# MCU.net
KiCad netlist of a schematic drawn in Altium Designer
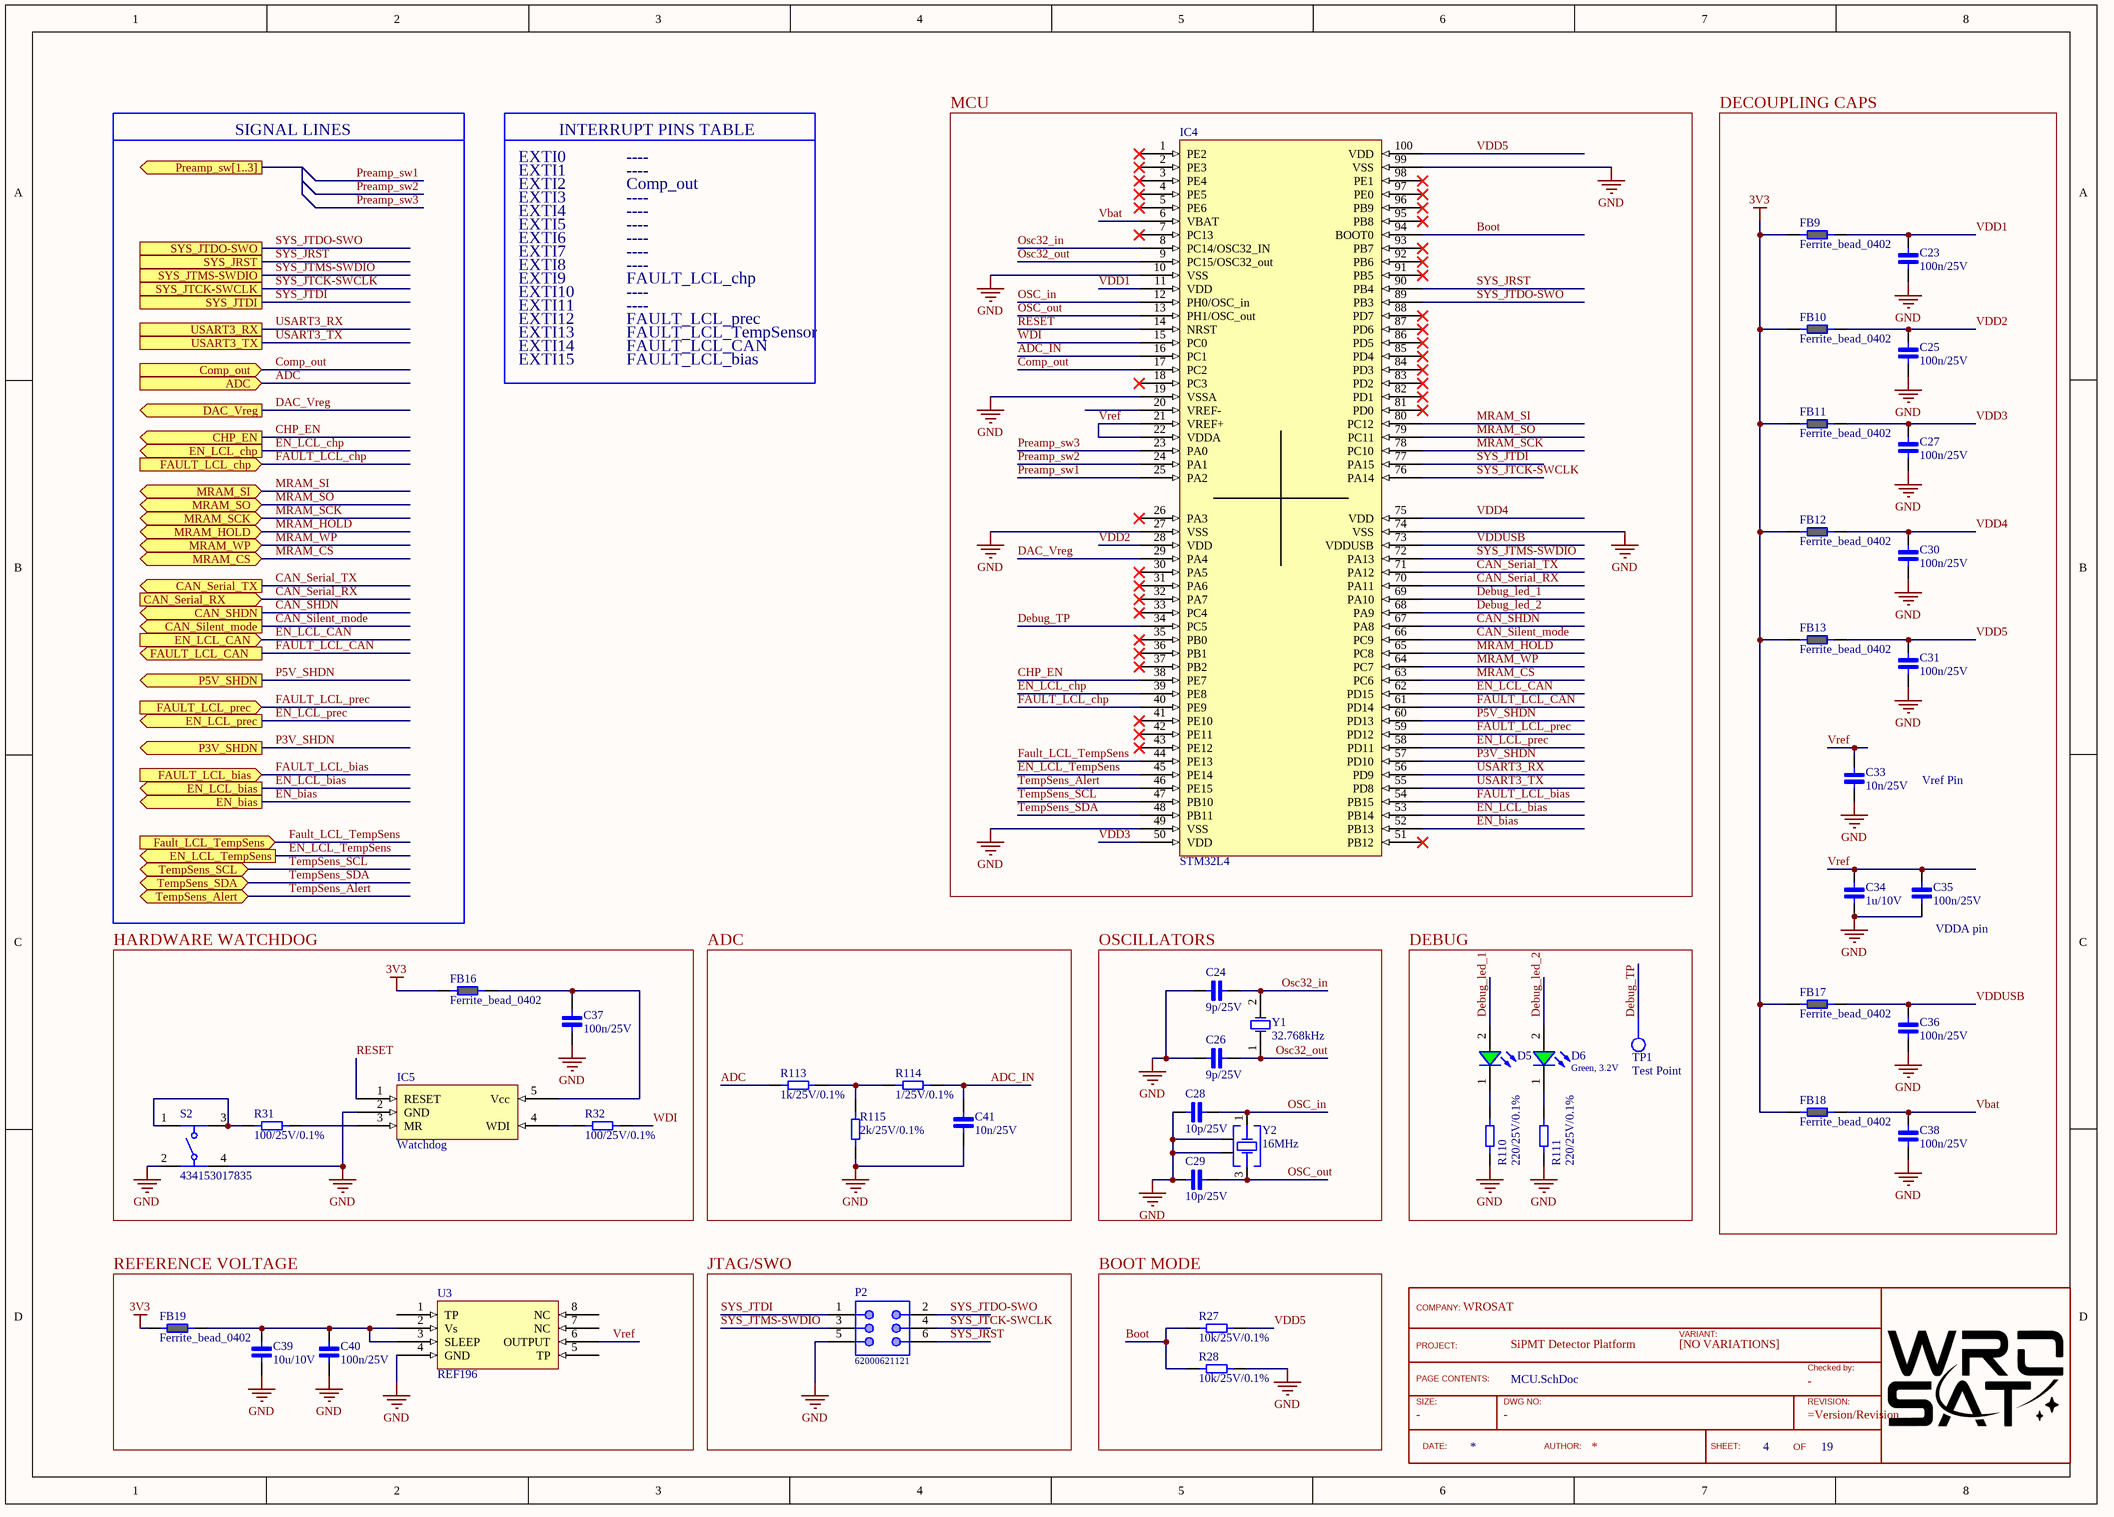
[diagram p0: MCU.SchDoc]

(export (version "E")
  (design (tool "Eeschema 10.0.6"))
  (components
    (comp (ref "C23")
      (value "100n/25V")
      (footprint "Cap_0402")
      (description "Ceramic Capacitor 100n / 0402 / 25V / ±5%, Wurth Elektronik MLCC")
      (libsource (lib "Cubesat_lib") (part "Cap_0402_100n"))
    )
    (comp (ref "C24")
      (value "9p/25V")
      (footprint "Cap_0402")
      (description "0402 / 25V / ±5%, Wurth Elektronik MLCC")
      (libsource (lib "Cubesat_lib") (part "Cap_0402_9p"))
    )
    (comp (ref "C25")
      (value "100n/25V")
      (footprint "Cap_0402")
      (description "Ceramic Capacitor 100n / 0402 / 25V / ±5%, Wurth Elektronik MLCC")
      (libsource (lib "Cubesat_lib") (part "Cap_0402_100n"))
    )
    (comp (ref "C26")
      (value "9p/25V")
      (footprint "Cap_0402")
      (description "0402 / 25V / ±5%, Wurth Elektronik MLCC")
      (libsource (lib "Cubesat_lib") (part "Cap_0402_9p"))
    )
    (comp (ref "C27")
      (value "100n/25V")
      (footprint "Cap_0402")
      (description "Ceramic Capacitor 100n / 0402 / 25V / ±5%, Wurth Elektronik MLCC")
      (libsource (lib "Cubesat_lib") (part "Cap_0402_100n"))
    )
    (comp (ref "C28")
      (value "10p/25V")
      (footprint "Cap_0402")
      (description "0402 / 25V / ±5%, Wurth Elektronik MLCC")
      (libsource (lib "Cubesat_lib") (part "Cap_0402_10p"))
    )
    (comp (ref "C29")
      (value "10p/25V")
      (footprint "Cap_0402")
      (description "0402 / 25V / ±5%, Wurth Elektronik MLCC")
      (libsource (lib "Cubesat_lib") (part "Cap_0402_10p"))
    )
    (comp (ref "C30")
      (value "100n/25V")
      (footprint "Cap_0402")
      (description "Ceramic Capacitor 100n / 0402 / 25V / ±5%, Wurth Elektronik MLCC")
      (libsource (lib "Cubesat_lib") (part "Cap_0402_100n"))
    )
    (comp (ref "C31")
      (value "100n/25V")
      (footprint "Cap_0402")
      (description "Ceramic Capacitor 100n / 0402 / 25V / ±5%, Wurth Elektronik MLCC")
      (libsource (lib "Cubesat_lib") (part "Cap_0402_100n"))
    )
    (comp (ref "C33")
      (value "10n/25V")
      (footprint "Cap_0402")
      (description "Ceramic Capacitor 10n / 0402 / 25V / ±5%, Wurth Elektronik MLCC")
      (libsource (lib "Cubesat_lib") (part "Cap_0402_10n"))
    )
    (comp (ref "C34")
      (value "1u/10V")
      (footprint "Cap_0402")
      (description "Ceramic Capacitor 1uF / 0402 / 10V / ±5%, Wurth Elektronik MLCC")
      (libsource (lib "Cubesat_lib") (part "Cap_0402_1u"))
    )
    (comp (ref "C35")
      (value "100n/25V")
      (footprint "Cap_0402")
      (description "Ceramic Capacitor 100n / 0402 / 25V / ±5%, Wurth Elektronik MLCC")
      (libsource (lib "Cubesat_lib") (part "Cap_0402_100n"))
    )
    (comp (ref "C36")
      (value "100n/25V")
      (footprint "Cap_0402")
      (description "Ceramic Capacitor 100n / 0402 / 25V / ±5%, Wurth Elektronik MLCC")
      (libsource (lib "Cubesat_lib") (part "Cap_0402_100n"))
    )
    (comp (ref "C37")
      (value "100n/25V")
      (footprint "Cap_0402")
      (description "Ceramic Capacitor 100n / 0402 / 25V / ±5%, Wurth Elektronik MLCC")
      (libsource (lib "Cubesat_lib") (part "Cap_0402_100n"))
    )
    (comp (ref "C38")
      (value "100n/25V")
      (footprint "Cap_0402")
      (description "Ceramic Capacitor 100n / 0402 / 25V / ±5%, Wurth Elektronik MLCC")
      (libsource (lib "Cubesat_lib") (part "Cap_0402_100n"))
    )
    (comp (ref "C39")
      (value "10u/10V")
      (footprint "CAP_0603")
      (description "Ceramic Capacitor 10uF / 0603 / 10V / ±5%, Wurth Elektronik MLCC")
      (libsource (lib "Cubesat_lib") (part "Cap_0603_10u"))
    )
    (comp (ref "C40")
      (value "100n/25V")
      (footprint "Cap_0402")
      (description "Ceramic Capacitor 100n / 0402 / 25V / ±5%, Wurth Elektronik MLCC")
      (libsource (lib "Cubesat_lib") (part "Cap_0402_100n"))
    )
    (comp (ref "C41")
      (value "10n/25V")
      (footprint "CAP_0603")
      (description "Ceramic Capacitor 10n / 0603 / 25V / ±5%, Wurth Elektronik MLCC")
      (libsource (lib "Cubesat_lib") (part "Cap_0603_10n"))
    )
    (comp (ref "D5")
      (value "Green, 3.2V")
      (footprint "WL-SMCW_0603_H=0.7mm")
      (description "WL-SMCW SMT Mono-color Chip LED Waterclear, size 0603, Green, 3.2V, 140deg")
      (fields (field (name "PART NUMBER") "150060GS75000") (field (name "PUBLISHER") "Wurth Elektronik"))
      (libsource (lib "LEDS") (part "150060GS75000"))
    )
    (comp (ref "D6")
      (value "Green, 3.2V")
      (footprint "WL-SMCW_0603_H=0.7mm")
      (description "WL-SMCW SMT Mono-color Chip LED Waterclear, size 0603, Green, 3.2V, 140deg")
      (fields (field (name "PART NUMBER") "150060GS75000") (field (name "PUBLISHER") "Wurth Elektronik"))
      (libsource (lib "LEDS") (part "150060GS75000"))
    )
    (comp (ref "FB9")
      (value "Ferrite_bead_0402")
      (footprint "FERRITE_0402")
      (description "Ferrite bead, wurth 74269241102")
      (libsource (lib "Cubesat_lib") (part "Ferrite_bead_0402"))
    )
    (comp (ref "FB10")
      (value "Ferrite_bead_0402")
      (footprint "FERRITE_0402")
      (description "Ferrite bead, wurth 74269241102")
      (libsource (lib "Cubesat_lib") (part "Ferrite_bead_0402"))
    )
    (comp (ref "FB11")
      (value "Ferrite_bead_0402")
      (footprint "FERRITE_0402")
      (description "Ferrite bead, wurth 74269241102")
      (libsource (lib "Cubesat_lib") (part "Ferrite_bead_0402"))
    )
    (comp (ref "FB12")
      (value "Ferrite_bead_0402")
      (footprint "FERRITE_0402")
      (description "Ferrite bead, wurth 74269241102")
      (libsource (lib "Cubesat_lib") (part "Ferrite_bead_0402"))
    )
    (comp (ref "FB13")
      (value "Ferrite_bead_0402")
      (footprint "FERRITE_0402")
      (description "Ferrite bead, wurth 74269241102")
      (libsource (lib "Cubesat_lib") (part "Ferrite_bead_0402"))
    )
    (comp (ref "FB16")
      (value "Ferrite_bead_0402")
      (footprint "FERRITE_0402")
      (description "Ferrite bead, wurth 74269241102")
      (libsource (lib "Cubesat_lib") (part "Ferrite_bead_0402"))
    )
    (comp (ref "FB17")
      (value "Ferrite_bead_0402")
      (footprint "FERRITE_0402")
      (description "Ferrite bead, wurth 74269241102")
      (libsource (lib "Cubesat_lib") (part "Ferrite_bead_0402"))
    )
    (comp (ref "FB18")
      (value "Ferrite_bead_0402")
      (footprint "FERRITE_0402")
      (description "Ferrite bead, wurth 74269241102")
      (libsource (lib "Cubesat_lib") (part "Ferrite_bead_0402"))
    )
    (comp (ref "FB19")
      (value "Ferrite_bead_0402")
      (footprint "FERRITE_0402")
      (description "Ferrite bead, wurth 74269241102")
      (libsource (lib "Cubesat_lib") (part "Ferrite_bead_0402"))
    )
    (comp (ref "IC4")
      (value "STM32L4")
      (footprint "LQFP100")
      (description "Microcontroller STM32")
      (libsource (lib "Cubesat_lib") (part "STM32L476VGT6"))
    )
    (comp (ref "IC5")
      (value "Watchdog")
      (footprint "SOT-23-5")
      (description "Watchdog, 5-Pin Microprocessor Supervisory Circuits With\r\nWatchdog Timer and Manual Reset")
      (libsource (lib "Cubesat_lib") (part "MAX823"))
    )
    (comp (ref "P2")
      (value "62000621121")
      (footprint "62000621121")
      (description "WR-PHD Pin Header, THT, pitch 2mm, Dual Row, Vertical, 6p")
      (fields (field (name "MANUFACTURER") "Wurth Elektronik"))
      (libsource (lib "goldpin") (part "62000621121"))
    )
    (comp (ref "R27")
      (value "10k/25V/0.1%")
      (footprint "RES_0402")
      (description "Vishay, thin film resistor 10k/25V/0.1%")
      (libsource (lib "Cubesat_lib") (part "Res_0402_10k"))
    )
    (comp (ref "R28")
      (value "10k/25V/0.1%")
      (footprint "RES_0402")
      (description "Vishay, thin film resistor 10k/25V/0.1%")
      (libsource (lib "Cubesat_lib") (part "Res_0402_10k"))
    )
    (comp (ref "R31")
      (value "100/25V/0.1%")
      (footprint "RES_0402")
      (description "Vishay, thin film resistor 100/25V/0.1%")
      (libsource (lib "Cubesat_lib") (part "Res_0402_100"))
    )
    (comp (ref "R32")
      (value "100/25V/0.1%")
      (footprint "RES_0402")
      (description "Vishay, thin film resistor 100/25V/0.1%")
      (libsource (lib "Cubesat_lib") (part "Res_0402_100"))
    )
    (comp (ref "R110")
      (value "220/25V/0.1%")
      (footprint "RES_0402")
      (description "Vishay, thin film resistor 1/25V/0.1%")
      (libsource (lib "Cubesat_lib") (part "Res_0402_1"))
    )
    (comp (ref "R111")
      (value "220/25V/0.1%")
      (footprint "RES_0402")
      (description "Vishay, thin film resistor 1/25V/0.1%")
      (libsource (lib "Cubesat_lib") (part "Res_0402_1"))
    )
    (comp (ref "R113")
      (value "1k/25V/0.1%")
      (footprint "RES_0402")
      (description "Vishay, thin film resistor 1k/25V/0.1%")
      (libsource (lib "Cubesat_lib") (part "Res_0402_1k"))
    )
    (comp (ref "R114")
      (value "1/25V/0.1%")
      (footprint "RES_0402")
      (description "Vishay, thin film resistor 1/25V/0.1%")
      (libsource (lib "") (part "Res_0402_1_1"))
    )
    (comp (ref "R115")
      (value "2k/25V/0.1%")
      (footprint "RES_0402")
      (description "Vishay, thin film resistor 2k/25V/0.1%")
      (libsource (lib "") (part "Res_0402_1k_1"))
    )
    (comp (ref "S2")
      (value "434153017835")
      (footprint "434153017835")
      (description "WS-TASV J-Bend SMT Tact Switch, 3.5x2.9x1.7mm, 350gf")
      (fields (field (name "MANUFACTURER") "Wurth Elektronik"))
      (libsource (lib "tact_switches") (part "434153017835"))
    )
    (comp (ref "TP1")
      (value "Test Point")
      (footprint "Test Point SMT")
      (libsource (lib "Cubesat_lib") (part "Test Point"))
    )
    (comp (ref "U3")
      (value "REF196")
      (footprint "SOIC8")
      (description "Precision Micropower,\r\nLow Dropout Voltage References")
      (libsource (lib "Cubesat_lib") (part "REF196"))
    )
    (comp (ref "Y1")
      (value "32.768kHz")
      (footprint "WE-XTAL_IQXC-25")
      (description "WE-XTAL Watch Crystal, SMT, IQXC-25, 32.768kHz, +/-10ppm")
      (fields
        (field (name "MANUFACTURER PART NUMBER") "830062558")
        (field (name "MANUFACTURER") "Wurth Elektronik")
      )
      (libsource (lib "32khz_crystal") (part "830062558"))
    )
    (comp (ref "Y2")
      (value "16MHz")
      (footprint "WE-XTAL_CFPX-218")
      (description "WE-XTAL Quartz Crystal, SMT, CFPX-218, 16MHz, +/-20ppm")
      (fields
        (field (name "MANUFACTURER PART NUMBER") "830069392")
        (field (name "MANUFACTURER") "Wurth Elektronik")
      )
      (libsource (lib "HSE_crystal") (part "830069392"))
    )
  )
  (nets
    (net (code "1") (name "/ADC") (class "Default")
      (node (ref "R113") (pin "1") (pinfunction "1_1") (pintype "passive"))
    )
    (net (code "2") (name "/ADC_IN") (class "Default")
      (node (ref "C41") (pin "2") (pinfunction "2_2") (pintype "passive"))
      (node (ref "IC4") (pin "16") (pinfunction "PC1_16") (pintype "input"))
      (node (ref "R114") (pin "2") (pinfunction "2_2") (pintype "passive"))
    )
    (net (code "3") (name "/Boot") (class "Default")
      (node (ref "IC4") (pin "94") (pinfunction "BOOT0_94") (pintype "input"))
      (node (ref "R27") (pin "1") (pinfunction "1_1") (pintype "passive"))
      (node (ref "R28") (pin "1") (pinfunction "1_1") (pintype "passive"))
    )
    (net (code "4") (name "/CAN_SHDN") (class "Default")
      (node (ref "IC4") (pin "67") (pinfunction "PA8_67") (pintype "input"))
    )
    (net (code "5") (name "/CAN_Serial_RX") (class "Default")
      (node (ref "IC4") (pin "70") (pinfunction "PA11_70") (pintype "input"))
    )
    (net (code "6") (name "/CAN_Serial_TX") (class "Default")
      (node (ref "IC4") (pin "71") (pinfunction "PA12_71") (pintype "input"))
    )
    (net (code "7") (name "/CAN_Silent_mode") (class "Default")
      (node (ref "IC4") (pin "66") (pinfunction "PC9_66") (pintype "input"))
    )
    (net (code "8") (name "/CHP_EN") (class "Default")
      (node (ref "IC4") (pin "38") (pinfunction "PE7_38") (pintype "input"))
    )
    (net (code "9") (name "/Comp_out") (class "Default")
      (node (ref "IC4") (pin "17") (pinfunction "PC2_17") (pintype "input"))
    )
    (net (code "10") (name "/DAC_Vreg") (class "Default")
      (node (ref "IC4") (pin "29") (pinfunction "PA4_29") (pintype "input"))
    )
    (net (code "11") (name "/Debug_TP") (class "Default")
      (node (ref "IC4") (pin "34") (pinfunction "PC5_34") (pintype "input"))
      (node (ref "TP1") (pin "1") (pinfunction "1_1") (pintype "passive"))
    )
    (net (code "12") (name "/Debug_led_1") (class "Default")
      (node (ref "D5") (pin "2") (pinfunction "A_2") (pintype "passive"))
      (node (ref "IC4") (pin "69") (pinfunction "PA10_69") (pintype "input"))
    )
    (net (code "13") (name "/Debug_led_2") (class "Default")
      (node (ref "D6") (pin "2") (pinfunction "A_2") (pintype "passive"))
      (node (ref "IC4") (pin "68") (pinfunction "PA9_68") (pintype "input"))
    )
    (net (code "14") (name "/EN_LCL_CAN") (class "Default")
      (node (ref "IC4") (pin "62") (pinfunction "PD15_62") (pintype "input"))
    )
    (net (code "15") (name "/EN_LCL_TempSens") (class "Default")
      (node (ref "IC4") (pin "45") (pinfunction "PE14_45") (pintype "input"))
    )
    (net (code "16") (name "/EN_LCL_bias") (class "Default")
      (node (ref "IC4") (pin "53") (pinfunction "PB14_53") (pintype "input"))
    )
    (net (code "17") (name "/EN_LCL_chp") (class "Default")
      (node (ref "IC4") (pin "39") (pinfunction "PE8_39") (pintype "input"))
    )
    (net (code "18") (name "/EN_LCL_prec") (class "Default")
      (node (ref "IC4") (pin "58") (pinfunction "PD11_58") (pintype "input"))
    )
    (net (code "19") (name "/EN_bias") (class "Default")
      (node (ref "IC4") (pin "52") (pinfunction "PB13_52") (pintype "input"))
    )
    (net (code "20") (name "/FAULT_LCL_CAN") (class "Default")
      (node (ref "IC4") (pin "61") (pinfunction "PD14_61") (pintype "input"))
    )
    (net (code "21") (name "/FAULT_LCL_bias") (class "Default")
      (node (ref "IC4") (pin "54") (pinfunction "PB15_54") (pintype "input"))
    )
    (net (code "22") (name "/FAULT_LCL_chp") (class "Default")
      (node (ref "IC4") (pin "40") (pinfunction "PE9_40") (pintype "input"))
    )
    (net (code "23") (name "/FAULT_LCL_prec") (class "Default")
      (node (ref "IC4") (pin "59") (pinfunction "PD12_59") (pintype "input"))
    )
    (net (code "24") (name "/Fault_LCL_TempSens") (class "Default")
      (node (ref "IC4") (pin "44") (pinfunction "PE13_44") (pintype "input"))
    )
    (net (code "25") (name "/MRAM_CS") (class "Default")
      (node (ref "IC4") (pin "63") (pinfunction "PC6_63") (pintype "input"))
    )
    (net (code "26") (name "/MRAM_HOLD") (class "Default")
      (node (ref "IC4") (pin "65") (pinfunction "PC8_65") (pintype "input"))
    )
    (net (code "27") (name "/MRAM_SCK") (class "Default")
      (node (ref "IC4") (pin "78") (pinfunction "PC10_78") (pintype "input"))
    )
    (net (code "28") (name "/MRAM_SI") (class "Default")
      (node (ref "IC4") (pin "80") (pinfunction "PC12_80") (pintype "input"))
    )
    (net (code "29") (name "/MRAM_SO") (class "Default")
      (node (ref "IC4") (pin "79") (pinfunction "PC11_79") (pintype "input"))
    )
    (net (code "30") (name "/MRAM_WP") (class "Default")
      (node (ref "IC4") (pin "64") (pinfunction "PC7_64") (pintype "input"))
    )
    (net (code "31") (name "/OSC_in") (class "Default")
      (node (ref "C28") (pin "2") (pinfunction "2_2") (pintype "passive"))
      (node (ref "IC4") (pin "12") (pinfunction "PH0/OSC_in_12") (pintype "input"))
      (node (ref "Y2") (pin "1") (pinfunction "Crystal_1") (pintype "passive"))
    )
    (net (code "32") (name "/OSC_out") (class "Default")
      (node (ref "C29") (pin "2") (pinfunction "2_2") (pintype "passive"))
      (node (ref "IC4") (pin "13") (pinfunction "PH1/OSC_out_13") (pintype "input"))
      (node (ref "Y2") (pin "3") (pinfunction "Crystal_3") (pintype "passive"))
    )
    (net (code "33") (name "/Osc32_in") (class "Default")
      (node (ref "C24") (pin "2") (pinfunction "2_2") (pintype "passive"))
      (node (ref "IC4") (pin "8") (pinfunction "PC14/OSC32_IN_8") (pintype "input"))
      (node (ref "Y1") (pin "2") (pinfunction "OSC2_2") (pintype "passive"))
    )
    (net (code "34") (name "/Osc32_out") (class "Default")
      (node (ref "C26") (pin "2") (pinfunction "2_2") (pintype "passive"))
      (node (ref "IC4") (pin "9") (pinfunction "PC15/OSC32_out_9") (pintype "input"))
      (node (ref "Y1") (pin "1") (pinfunction "OSC1_1") (pintype "passive"))
    )
    (net (code "35") (name "/P3V_SHDN") (class "Default")
      (node (ref "IC4") (pin "57") (pinfunction "PD10_57") (pintype "input"))
    )
    (net (code "36") (name "/P5V_SHDN") (class "Default")
      (node (ref "IC4") (pin "60") (pinfunction "PD13_60") (pintype "input"))
    )
    (net (code "37") (name "/Preamp_sw1") (class "Default")
      (node (ref "IC4") (pin "25") (pinfunction "PA2_25") (pintype "input"))
    )
    (net (code "38") (name "/Preamp_sw2") (class "Default")
      (node (ref "IC4") (pin "24") (pinfunction "PA1_24") (pintype "input"))
    )
    (net (code "39") (name "/Preamp_sw3") (class "Default")
      (node (ref "IC4") (pin "23") (pinfunction "PA0_23") (pintype "input"))
    )
    (net (code "41") (name "/RESET") (class "Default")
      (node (ref "IC4") (pin "14") (pinfunction "NRST_14") (pintype "input"))
      (node (ref "IC5") (pin "1") (pinfunction "RESET_1") (pintype "input"))
    )
    (net (code "42") (name "/SYS_JRST") (class "Default")
      (node (ref "IC4") (pin "90") (pinfunction "PB4_90") (pintype "input"))
      (node (ref "P2") (pin "6") (pinfunction "6_6") (pintype "passive"))
    )
    (net (code "43") (name "/SYS_JTCK-SWCLK") (class "Default")
      (node (ref "IC4") (pin "76") (pinfunction "PA14_76") (pintype "input"))
      (node (ref "P2") (pin "4") (pinfunction "4_4") (pintype "passive"))
    )
    (net (code "44") (name "/SYS_JTDI") (class "Default")
      (node (ref "IC4") (pin "77") (pinfunction "PA15_77") (pintype "input"))
      (node (ref "P2") (pin "1") (pinfunction "1_1") (pintype "passive"))
    )
    (net (code "45") (name "/SYS_JTDO-SWO") (class "Default")
      (node (ref "IC4") (pin "89") (pinfunction "PB3_89") (pintype "input"))
      (node (ref "P2") (pin "2") (pinfunction "2_2") (pintype "passive"))
    )
    (net (code "46") (name "/SYS_JTMS-SWDIO") (class "Default")
      (node (ref "IC4") (pin "72") (pinfunction "PA13_72") (pintype "input"))
      (node (ref "P2") (pin "3") (pinfunction "3_3") (pintype "passive"))
    )
    (net (code "47") (name "/TempSens_Alert") (class "Default")
      (node (ref "IC4") (pin "46") (pinfunction "PE15_46") (pintype "input"))
    )
    (net (code "48") (name "/TempSens_SCL") (class "Default")
      (node (ref "IC4") (pin "47") (pinfunction "PB10_47") (pintype "input"))
    )
    (net (code "49") (name "/TempSens_SDA") (class "Default")
      (node (ref "IC4") (pin "48") (pinfunction "PB11_48") (pintype "input"))
    )
    (net (code "50") (name "/USART3_RX") (class "Default")
      (node (ref "IC4") (pin "56") (pinfunction "PD9_56") (pintype "input"))
    )
    (net (code "51") (name "/USART3_TX") (class "Default")
      (node (ref "IC4") (pin "55") (pinfunction "PD8_55") (pintype "input"))
    )
    (net (code "52") (name "/VDD1") (class "Default")
      (node (ref "C23") (pin "2") (pinfunction "2_2") (pintype "passive"))
      (node (ref "FB9") (pin "2") (pinfunction "2_2") (pintype "passive"))
      (node (ref "IC4") (pin "11") (pinfunction "VDD_11") (pintype "input"))
    )
    (net (code "53") (name "/VDD2") (class "Default")
      (node (ref "C25") (pin "2") (pinfunction "2_2") (pintype "passive"))
      (node (ref "FB10") (pin "2") (pinfunction "2_2") (pintype "passive"))
      (node (ref "IC4") (pin "28") (pinfunction "VDD_28") (pintype "input"))
    )
    (net (code "54") (name "/VDD3") (class "Default")
      (node (ref "C27") (pin "2") (pinfunction "2_2") (pintype "passive"))
      (node (ref "FB11") (pin "2") (pinfunction "2_2") (pintype "passive"))
      (node (ref "IC4") (pin "50") (pinfunction "VDD_50") (pintype "input"))
    )
    (net (code "55") (name "/VDD4") (class "Default")
      (node (ref "C30") (pin "2") (pinfunction "2_2") (pintype "passive"))
      (node (ref "FB12") (pin "2") (pinfunction "2_2") (pintype "passive"))
      (node (ref "IC4") (pin "75") (pinfunction "VDD_75") (pintype "input"))
    )
    (net (code "56") (name "/VDD5") (class "Default")
      (node (ref "C31") (pin "2") (pinfunction "2_2") (pintype "passive"))
      (node (ref "FB13") (pin "2") (pinfunction "2_2") (pintype "passive"))
      (node (ref "IC4") (pin "100") (pinfunction "VDD_100") (pintype "input"))
      (node (ref "R27") (pin "2") (pinfunction "2_2") (pintype "passive"))
    )
    (net (code "57") (name "/VDDUSB") (class "Default")
      (node (ref "C36") (pin "2") (pinfunction "2_2") (pintype "passive"))
      (node (ref "FB17") (pin "2") (pinfunction "2_2") (pintype "passive"))
      (node (ref "IC4") (pin "73") (pinfunction "VDDUSB_73") (pintype "input"))
    )
    (net (code "58") (name "/Vbat") (class "Default")
      (node (ref "C38") (pin "2") (pinfunction "2_2") (pintype "passive"))
      (node (ref "FB18") (pin "2") (pinfunction "2_2") (pintype "passive"))
      (node (ref "IC4") (pin "6") (pinfunction "VBAT_6") (pintype "input"))
    )
    (net (code "59") (name "/Vref") (class "Default")
      (node (ref "C33") (pin "2") (pinfunction "2_2") (pintype "passive"))
      (node (ref "C34") (pin "2") (pinfunction "2_2") (pintype "passive"))
      (node (ref "C35") (pin "2") (pinfunction "2_2") (pintype "passive"))
      (node (ref "IC4") (pin "21") (pinfunction "VREF+_21") (pintype "input"))
      (node (ref "IC4") (pin "22") (pinfunction "VDDA_22") (pintype "input"))
      (node (ref "U3") (pin "6") (pinfunction "OUTPUT_6") (pintype "input"))
    )
    (net (code "60") (name "/WDI") (class "Default")
      (node (ref "IC4") (pin "15") (pinfunction "PC0_15") (pintype "input"))
      (node (ref "R32") (pin "2") (pinfunction "2_2") (pintype "passive"))
    )
    (net (code "61") (name "3V3") (class "Default")
      (node (ref "FB10") (pin "1") (pinfunction "1_1") (pintype "passive"))
      (node (ref "FB11") (pin "1") (pinfunction "1_1") (pintype "passive"))
      (node (ref "FB12") (pin "1") (pinfunction "1_1") (pintype "passive"))
      (node (ref "FB13") (pin "1") (pinfunction "1_1") (pintype "passive"))
      (node (ref "FB16") (pin "1") (pinfunction "1_1") (pintype "passive"))
      (node (ref "FB17") (pin "1") (pinfunction "1_1") (pintype "passive"))
      (node (ref "FB18") (pin "1") (pinfunction "1_1") (pintype "passive"))
      (node (ref "FB19") (pin "1") (pinfunction "1_1") (pintype "passive"))
      (node (ref "FB9") (pin "1") (pinfunction "1_1") (pintype "passive"))
    )
    (net (code "62") (name "GND") (class "Default")
      (node (ref "C23") (pin "1") (pinfunction "1_1") (pintype "passive"))
      (node (ref "C24") (pin "1") (pinfunction "1_1") (pintype "passive"))
      (node (ref "C25") (pin "1") (pinfunction "1_1") (pintype "passive"))
      (node (ref "C26") (pin "1") (pinfunction "1_1") (pintype "passive"))
      (node (ref "C27") (pin "1") (pinfunction "1_1") (pintype "passive"))
      (node (ref "C28") (pin "1") (pinfunction "1_1") (pintype "passive"))
      (node (ref "C29") (pin "1") (pinfunction "1_1") (pintype "passive"))
      (node (ref "C30") (pin "1") (pinfunction "1_1") (pintype "passive"))
      (node (ref "C31") (pin "1") (pinfunction "1_1") (pintype "passive"))
      (node (ref "C33") (pin "1") (pinfunction "1_1") (pintype "passive"))
      (node (ref "C34") (pin "1") (pinfunction "1_1") (pintype "passive"))
      (node (ref "C35") (pin "1") (pinfunction "1_1") (pintype "passive"))
      (node (ref "C36") (pin "1") (pinfunction "1_1") (pintype "passive"))
      (node (ref "C37") (pin "1") (pinfunction "1_1") (pintype "passive"))
      (node (ref "C38") (pin "1") (pinfunction "1_1") (pintype "passive"))
      (node (ref "C39") (pin "1") (pinfunction "1_1") (pintype "passive"))
      (node (ref "C40") (pin "1") (pinfunction "1_1") (pintype "passive"))
      (node (ref "C41") (pin "1") (pinfunction "1_1") (pintype "passive"))
      (node (ref "IC4") (pin "10") (pinfunction "VSS_10") (pintype "input"))
      (node (ref "IC4") (pin "19") (pinfunction "VSSA_19") (pintype "input"))
      (node (ref "IC4") (pin "27") (pinfunction "VSS_27") (pintype "input"))
      (node (ref "IC4") (pin "49") (pinfunction "VSS_49") (pintype "input"))
      (node (ref "IC4") (pin "74") (pinfunction "VSS_74") (pintype "input"))
      (node (ref "IC4") (pin "99") (pinfunction "VSS_99") (pintype "input"))
      (node (ref "IC5") (pin "2") (pinfunction "GND_2") (pintype "input"))
      (node (ref "P2") (pin "5") (pinfunction "5_5") (pintype "passive"))
      (node (ref "R110") (pin "1") (pinfunction "1_1") (pintype "passive"))
      (node (ref "R111") (pin "1") (pinfunction "1_1") (pintype "passive"))
      (node (ref "R115") (pin "1") (pinfunction "1_1") (pintype "passive"))
      (node (ref "R28") (pin "2") (pinfunction "2_2") (pintype "passive"))
      (node (ref "S2") (pin "2") (pinfunction "2_2") (pintype "passive"))
      (node (ref "S2") (pin "4") (pinfunction "4_4") (pintype "passive"))
      (node (ref "U3") (pin "4") (pinfunction "GND_4") (pintype "input"))
      (node (ref "Y2") (pin "2") (pinfunction "GND_2") (pintype "passive"))
      (node (ref "Y2") (pin "4") (pinfunction "GND_4") (pintype "passive"))
    )
    (net (code "63") (name "Net-(D5-K)") (class "Default")
      (node (ref "D5") (pin "1") (pinfunction "K_1") (pintype "passive"))
      (node (ref "R110") (pin "2") (pinfunction "2_2") (pintype "passive"))
    )
    (net (code "64") (name "Net-(D6-K)") (class "Default")
      (node (ref "D6") (pin "1") (pinfunction "K_1") (pintype "passive"))
      (node (ref "R111") (pin "2") (pinfunction "2_2") (pintype "passive"))
    )
    (net (code "65") (name "Net-(IC5-MR)") (class "Default")
      (node (ref "IC5") (pin "3") (pinfunction "MR_3") (pintype "input"))
      (node (ref "R31") (pin "2") (pinfunction "2_2") (pintype "passive"))
    )
    (net (code "66") (name "Net-(IC5-Vcc)") (class "Default")
      (node (ref "C37") (pin "2") (pinfunction "2_2") (pintype "passive"))
      (node (ref "FB16") (pin "2") (pinfunction "2_2") (pintype "passive"))
      (node (ref "IC5") (pin "5") (pinfunction "Vcc_5") (pintype "input"))
    )
    (net (code "67") (name "Net-(IC5-WDI)") (class "Default")
      (node (ref "IC5") (pin "4") (pinfunction "WDI_4") (pintype "input"))
      (node (ref "R32") (pin "1") (pinfunction "1_1") (pintype "passive"))
    )
    (net (code "68") (name "Net-(R31-Pad1)") (class "Default")
      (node (ref "R31") (pin "1") (pinfunction "1_1") (pintype "passive"))
      (node (ref "S2") (pin "1") (pinfunction "1_1") (pintype "passive"))
      (node (ref "S2") (pin "3") (pinfunction "3_3") (pintype "passive"))
    )
    (net (code "69") (name "Net-(R113-Pad2)") (class "Default")
      (node (ref "R113") (pin "2") (pinfunction "2_2") (pintype "passive"))
      (node (ref "R114") (pin "1") (pinfunction "1_1") (pintype "passive"))
      (node (ref "R115") (pin "2") (pinfunction "2_2") (pintype "passive"))
    )
    (net (code "70") (name "Net-(U3-SLEEP)") (class "Default")
      (node (ref "C39") (pin "2") (pinfunction "2_2") (pintype "passive"))
      (node (ref "C40") (pin "2") (pinfunction "2_2") (pintype "passive"))
      (node (ref "FB19") (pin "2") (pinfunction "2_2") (pintype "passive"))
      (node (ref "U3") (pin "2") (pinfunction "Vs_2") (pintype "input"))
      (node (ref "U3") (pin "3") (pinfunction "SLEEP_3") (pintype "input"))
    )
    (net (code "71") (name "unconnected-(IC4-PA3-Pad26)") (class "Default")
      (node (ref "IC4") (pin "26") (pinfunction "PA3_26") (pintype "input+no_connect"))
    )
    (net (code "72") (name "unconnected-(IC4-PA5-Pad30)") (class "Default")
      (node (ref "IC4") (pin "30") (pinfunction "PA5_30") (pintype "input+no_connect"))
    )
    (net (code "73") (name "unconnected-(IC4-PA6-Pad31)") (class "Default")
      (node (ref "IC4") (pin "31") (pinfunction "PA6_31") (pintype "input+no_connect"))
    )
    (net (code "74") (name "unconnected-(IC4-PA7-Pad32)") (class "Default")
      (node (ref "IC4") (pin "32") (pinfunction "PA7_32") (pintype "input+no_connect"))
    )
    (net (code "75") (name "unconnected-(IC4-PB0-Pad35)") (class "Default")
      (node (ref "IC4") (pin "35") (pinfunction "PB0_35") (pintype "input+no_connect"))
    )
    (net (code "76") (name "unconnected-(IC4-PB1-Pad36)") (class "Default")
      (node (ref "IC4") (pin "36") (pinfunction "PB1_36") (pintype "input+no_connect"))
    )
    (net (code "77") (name "unconnected-(IC4-PB2-Pad37)") (class "Default")
      (node (ref "IC4") (pin "37") (pinfunction "PB2_37") (pintype "input+no_connect"))
    )
    (net (code "78") (name "unconnected-(IC4-PB5-Pad91)") (class "Default")
      (node (ref "IC4") (pin "91") (pinfunction "PB5_91") (pintype "input+no_connect"))
    )
    (net (code "79") (name "unconnected-(IC4-PB6-Pad92)") (class "Default")
      (node (ref "IC4") (pin "92") (pinfunction "PB6_92") (pintype "input+no_connect"))
    )
    (net (code "80") (name "unconnected-(IC4-PB7-Pad93)") (class "Default")
      (node (ref "IC4") (pin "93") (pinfunction "PB7_93") (pintype "input+no_connect"))
    )
    (net (code "81") (name "unconnected-(IC4-PB8-Pad95)") (class "Default")
      (node (ref "IC4") (pin "95") (pinfunction "PB8_95") (pintype "input+no_connect"))
    )
    (net (code "82") (name "unconnected-(IC4-PB9-Pad96)") (class "Default")
      (node (ref "IC4") (pin "96") (pinfunction "PB9_96") (pintype "input+no_connect"))
    )
    (net (code "83") (name "unconnected-(IC4-PB12-Pad51)") (class "Default")
      (node (ref "IC4") (pin "51") (pinfunction "PB12_51") (pintype "input+no_connect"))
    )
    (net (code "84") (name "unconnected-(IC4-PC3-Pad18)") (class "Default")
      (node (ref "IC4") (pin "18") (pinfunction "PC3_18") (pintype "input+no_connect"))
    )
    (net (code "85") (name "unconnected-(IC4-PC4-Pad33)") (class "Default")
      (node (ref "IC4") (pin "33") (pinfunction "PC4_33") (pintype "input+no_connect"))
    )
    (net (code "86") (name "unconnected-(IC4-PC13-Pad7)") (class "Default")
      (node (ref "IC4") (pin "7") (pinfunction "PC13_7") (pintype "input+no_connect"))
    )
    (net (code "87") (name "unconnected-(IC4-PD0-Pad81)") (class "Default")
      (node (ref "IC4") (pin "81") (pinfunction "PD0_81") (pintype "input+no_connect"))
    )
    (net (code "88") (name "unconnected-(IC4-PD1-Pad82)") (class "Default")
      (node (ref "IC4") (pin "82") (pinfunction "PD1_82") (pintype "input+no_connect"))
    )
    (net (code "89") (name "unconnected-(IC4-PD2-Pad83)") (class "Default")
      (node (ref "IC4") (pin "83") (pinfunction "PD2_83") (pintype "input+no_connect"))
    )
    (net (code "90") (name "unconnected-(IC4-PD3-Pad84)") (class "Default")
      (node (ref "IC4") (pin "84") (pinfunction "PD3_84") (pintype "input+no_connect"))
    )
    (net (code "91") (name "unconnected-(IC4-PD4-Pad85)") (class "Default")
      (node (ref "IC4") (pin "85") (pinfunction "PD4_85") (pintype "input+no_connect"))
    )
    (net (code "92") (name "unconnected-(IC4-PD5-Pad86)") (class "Default")
      (node (ref "IC4") (pin "86") (pinfunction "PD5_86") (pintype "input+no_connect"))
    )
    (net (code "93") (name "unconnected-(IC4-PD6-Pad87)") (class "Default")
      (node (ref "IC4") (pin "87") (pinfunction "PD6_87") (pintype "input+no_connect"))
    )
    (net (code "94") (name "unconnected-(IC4-PD7-Pad88)") (class "Default")
      (node (ref "IC4") (pin "88") (pinfunction "PD7_88") (pintype "input+no_connect"))
    )
    (net (code "95") (name "unconnected-(IC4-PE0-Pad97)") (class "Default")
      (node (ref "IC4") (pin "97") (pinfunction "PE0_97") (pintype "input+no_connect"))
    )
    (net (code "96") (name "unconnected-(IC4-PE1-Pad98)") (class "Default")
      (node (ref "IC4") (pin "98") (pinfunction "PE1_98") (pintype "input+no_connect"))
    )
    (net (code "97") (name "unconnected-(IC4-PE2-Pad1)") (class "Default")
      (node (ref "IC4") (pin "1") (pinfunction "PE2_1") (pintype "input+no_connect"))
    )
    (net (code "98") (name "unconnected-(IC4-PE3-Pad2)") (class "Default")
      (node (ref "IC4") (pin "2") (pinfunction "PE3_2") (pintype "input+no_connect"))
    )
    (net (code "99") (name "unconnected-(IC4-PE4-Pad3)") (class "Default")
      (node (ref "IC4") (pin "3") (pinfunction "PE4_3") (pintype "input+no_connect"))
    )
    (net (code "100") (name "unconnected-(IC4-PE5-Pad4)") (class "Default")
      (node (ref "IC4") (pin "4") (pinfunction "PE5_4") (pintype "input+no_connect"))
    )
    (net (code "101") (name "unconnected-(IC4-PE6-Pad5)") (class "Default")
      (node (ref "IC4") (pin "5") (pinfunction "PE6_5") (pintype "input+no_connect"))
    )
    (net (code "102") (name "unconnected-(IC4-PE10-Pad41)") (class "Default")
      (node (ref "IC4") (pin "41") (pinfunction "PE10_41") (pintype "input+no_connect"))
    )
    (net (code "103") (name "unconnected-(IC4-PE11-Pad42)") (class "Default")
      (node (ref "IC4") (pin "42") (pinfunction "PE11_42") (pintype "input+no_connect"))
    )
    (net (code "104") (name "unconnected-(IC4-PE12-Pad43)") (class "Default")
      (node (ref "IC4") (pin "43") (pinfunction "PE12_43") (pintype "input+no_connect"))
    )
    (net (code "105") (name "unconnected-(IC4-VREF--Pad20)") (class "Default")
      (node (ref "IC4") (pin "20") (pinfunction "VREF-_20") (pintype "input"))
    )
    (net (code "106") (name "unconnected-(U3-NC-Pad7)") (class "Default")
      (node (ref "U3") (pin "7") (pinfunction "NC_7") (pintype "input"))
    )
    (net (code "107") (name "unconnected-(U3-NC-Pad8)") (class "Default")
      (node (ref "U3") (pin "8") (pinfunction "NC_8") (pintype "input"))
    )
    (net (code "108") (name "unconnected-(U3-TP-Pad1)") (class "Default")
      (node (ref "U3") (pin "1") (pinfunction "TP_1") (pintype "input"))
    )
    (net (code "109") (name "unconnected-(U3-TP-Pad5)") (class "Default")
      (node (ref "U3") (pin "5") (pinfunction "TP_5") (pintype "input"))
    )
  )
)
